# D1_-_LCD_TH_Screws.net
KiCad netlist of a schematic drawn in EAGLE
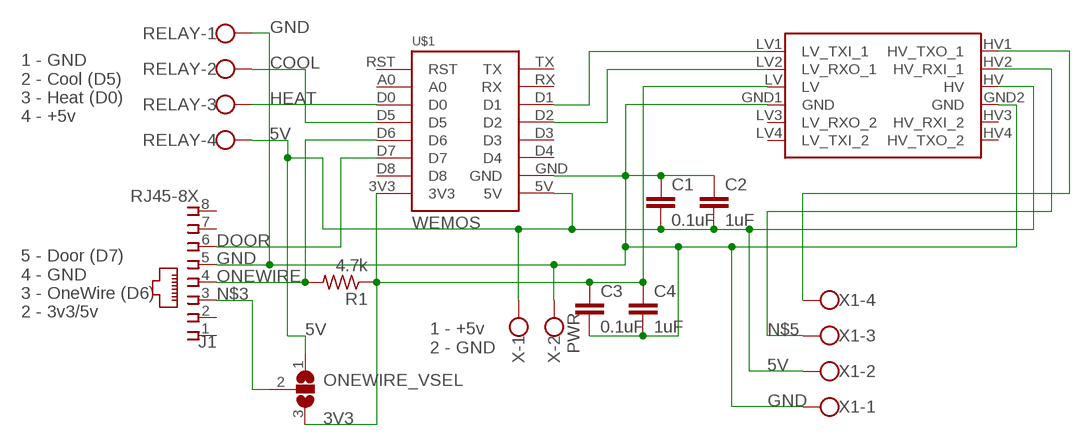
[diagram p0: schematic, sheet 1]

(export (version "E")
  (design (tool "Eeschema 10.0.6"))
  (components
    (comp (ref "C1")
      (value "0.1uF")
      (footprint "eagle-import:C050-035X075")
      (libsource (lib "eagle-import") (part "C-EU050-035X075"))
    )
    (comp (ref "C2")
      (value "1uF")
      (footprint "eagle-import:C050-035X075")
      (libsource (lib "eagle-import") (part "C-EU050-035X075"))
    )
    (comp (ref "C3")
      (value "0.1uF")
      (footprint "eagle-import:C050-035X075")
      (libsource (lib "eagle-import") (part "C-EU050-035X075"))
    )
    (comp (ref "C4")
      (value "1uF")
      (footprint "eagle-import:C050-035X075")
      (libsource (lib "eagle-import") (part "C-EU050-035X075"))
    )
    (comp (ref "J1")
      (value "RJ45-8X")
      (footprint "eagle-import:RJ45-NS-XDIM")
      (libsource (lib "eagle-import") (part "RJ45-8X"))
    )
    (comp (ref "ONEWIRE_VSEL")
      (value "SJ2WW")
      (footprint "eagle-import:SJ_2W")
      (libsource (lib "eagle-import") (part "SJ2WW"))
    )
    (comp (ref "R1")
      (value "4.7k")
      (footprint "eagle-import:0309_12")
      (libsource (lib "eagle-import") (part "R-US_0309/12"))
    )
    (comp (ref "RELAY")
      (value "W237-4")
      (footprint "eagle-import:W237-4")
      (libsource (lib "eagle-import") (part "W237-4"))
    )
    (comp (ref "U$1")
      (value "WEMOS")
      (footprint "eagle-import:WEMOS")
      (libsource (lib "eagle-import") (part "WEMOS"))
    )
    (comp (ref "U$3")
      (value "SPARKFUN_LOGIC_LEVEL_CONVERTER")
      (footprint "eagle-import:SPARKFUN_LOGIC_LEVEL_CONVERTER")
      (libsource (lib "eagle-import") (part "SPARKFUN_LOGIC_LEVEL_CONVERTER"))
    )
    (comp (ref "X")
      (value "PWR")
      (footprint "eagle-import:W237-102")
      (fields (field (name "MPN") "237-102"))
      (libsource (lib "eagle-import") (part "W237-102"))
    )
    (comp (ref "X1")
      (value "W237-4")
      (footprint "eagle-import:W237-4")
      (libsource (lib "eagle-import") (part "W237-4"))
    )
  )
  (nets
    (net (code "1") (name "/3V3") (class "Default")
      (node (ref "C3") (pin "1") (pinfunction "1_1") (pintype "passive"))
      (node (ref "C4") (pin "1") (pinfunction "1_1") (pintype "passive"))
      (node (ref "ONEWIRE_VSEL") (pin "3") (pinfunction "3_3") (pintype "passive"))
      (node (ref "R1") (pin "1") (pinfunction "1_1") (pintype "passive"))
      (node (ref "U$1") (pin "3V3") (pinfunction "3V3_3V3") (pintype "bidirectional"))
      (node (ref "U$3") (pin "LV") (pinfunction "LV_LV") (pintype "power_in"))
    )
    (net (code "2") (name "/5V") (class "Default")
      (node (ref "C1") (pin "2") (pinfunction "2_2") (pintype "passive"))
      (node (ref "C2") (pin "2") (pinfunction "2_2") (pintype "passive"))
      (node (ref "ONEWIRE_VSEL") (pin "1") (pinfunction "1_1") (pintype "passive"))
      (node (ref "RELAY") (pin "4") (pinfunction "KL_4") (pintype "passive"))
      (node (ref "U$1") (pin "5V") (pinfunction "5V_5V") (pintype "bidirectional"))
      (node (ref "U$3") (pin "HV") (pinfunction "HV_HV") (pintype "power_in"))
      (node (ref "X") (pin "1") (pinfunction "KL_1") (pintype "passive"))
      (node (ref "X1") (pin "2") (pinfunction "KL_2") (pintype "passive"))
    )
    (net (code "3") (name "/COOL") (class "Default")
      (node (ref "RELAY") (pin "2") (pinfunction "KL_2") (pintype "passive"))
      (node (ref "U$1") (pin "D5") (pinfunction "D5_D5") (pintype "bidirectional"))
    )
    (net (code "4") (name "/DOOR") (class "Default")
      (node (ref "J1") (pin "6") (pinfunction "6_6") (pintype "passive"))
      (node (ref "U$1") (pin "D7") (pinfunction "D7_D7") (pintype "bidirectional"))
    )
    (net (code "5") (name "/GND") (class "Default")
      (node (ref "C1") (pin "1") (pinfunction "1_1") (pintype "passive"))
      (node (ref "C2") (pin "1") (pinfunction "1_1") (pintype "passive"))
      (node (ref "C3") (pin "2") (pinfunction "2_2") (pintype "passive"))
      (node (ref "C4") (pin "2") (pinfunction "2_2") (pintype "passive"))
      (node (ref "J1") (pin "5") (pinfunction "5_5") (pintype "passive"))
      (node (ref "RELAY") (pin "1") (pinfunction "KL_1") (pintype "passive"))
      (node (ref "U$1") (pin "GND") (pinfunction "GND_GND") (pintype "bidirectional"))
      (node (ref "U$3") (pin "GND1") (pinfunction "GND_GND1") (pintype "power_in"))
      (node (ref "U$3") (pin "GND2") (pinfunction "GND_GND2") (pintype "power_in"))
      (node (ref "X") (pin "2") (pinfunction "KL_2") (pintype "passive"))
      (node (ref "X1") (pin "1") (pinfunction "KL_1") (pintype "passive"))
    )
    (net (code "6") (name "/HEAT") (class "Default")
      (node (ref "RELAY") (pin "3") (pinfunction "KL_3") (pintype "passive"))
      (node (ref "U$1") (pin "D0") (pinfunction "D0_D0") (pintype "bidirectional"))
    )
    (net (code "7") (name "/N$3") (class "Default")
      (node (ref "J1") (pin "3") (pinfunction "3_3") (pintype "passive"))
      (node (ref "ONEWIRE_VSEL") (pin "2") (pinfunction "2_2") (pintype "passive"))
    )
    (net (code "8") (name "/N$5") (class "Default")
      (node (ref "U$3") (pin "HV2") (pinfunction "HV_RXI_1_HV2") (pintype "bidirectional"))
      (node (ref "X1") (pin "3") (pinfunction "KL_3") (pintype "passive"))
    )
    (net (code "9") (name "/ONEWIRE") (class "Default")
      (node (ref "J1") (pin "4") (pinfunction "4_4") (pintype "passive"))
      (node (ref "R1") (pin "2") (pinfunction "2_2") (pintype "passive"))
      (node (ref "U$1") (pin "D6") (pinfunction "D6_D6") (pintype "bidirectional"))
    )
    (net (code "10") (name "Net-(U$3-HV_TXO_1)") (class "Default")
      (node (ref "U$3") (pin "HV1") (pinfunction "HV_TXO_1_HV1") (pintype "bidirectional"))
      (node (ref "X1") (pin "4") (pinfunction "KL_4") (pintype "passive"))
    )
    (net (code "11") (name "Net-(U$3-LV_RXO_1)") (class "Default")
      (node (ref "U$1") (pin "D2") (pinfunction "D2_D2") (pintype "bidirectional"))
      (node (ref "U$3") (pin "LV2") (pinfunction "LV_RXO_1_LV2") (pintype "bidirectional"))
    )
    (net (code "12") (name "Net-(U$3-LV_TXI_1)") (class "Default")
      (node (ref "U$1") (pin "D1") (pinfunction "D1_D1") (pintype "bidirectional"))
      (node (ref "U$3") (pin "LV1") (pinfunction "LV_TXI_1_LV1") (pintype "bidirectional"))
    )
    (net (code "13") (name "unconnected-(J1-Pad1)") (class "Default")
      (node (ref "J1") (pin "1") (pinfunction "1_1") (pintype "passive"))
    )
    (net (code "14") (name "unconnected-(J1-Pad2)") (class "Default")
      (node (ref "J1") (pin "2") (pinfunction "2_2") (pintype "passive"))
    )
    (net (code "15") (name "unconnected-(J1-Pad7)") (class "Default")
      (node (ref "J1") (pin "7") (pinfunction "7_7") (pintype "passive"))
    )
    (net (code "16") (name "unconnected-(J1-Pad8)") (class "Default")
      (node (ref "J1") (pin "8") (pinfunction "8_8") (pintype "passive"))
    )
    (net (code "17") (name "unconnected-(U$1-PadA0)") (class "Default")
      (node (ref "U$1") (pin "A0") (pinfunction "A0_A0") (pintype "bidirectional"))
    )
    (net (code "18") (name "unconnected-(U$1-PadD3)") (class "Default")
      (node (ref "U$1") (pin "D3") (pinfunction "D3_D3") (pintype "bidirectional"))
    )
    (net (code "19") (name "unconnected-(U$1-PadD4)") (class "Default")
      (node (ref "U$1") (pin "D4") (pinfunction "D4_D4") (pintype "bidirectional"))
    )
    (net (code "20") (name "unconnected-(U$1-PadD8)") (class "Default")
      (node (ref "U$1") (pin "D8") (pinfunction "D8_D8") (pintype "bidirectional"))
    )
    (net (code "21") (name "unconnected-(U$1-PadRST)") (class "Default")
      (node (ref "U$1") (pin "RST") (pinfunction "RST_RST") (pintype "bidirectional"))
    )
    (net (code "22") (name "unconnected-(U$1-PadRX)") (class "Default")
      (node (ref "U$1") (pin "RX") (pinfunction "RX_RX") (pintype "bidirectional"))
    )
    (net (code "23") (name "unconnected-(U$1-PadTX)") (class "Default")
      (node (ref "U$1") (pin "TX") (pinfunction "TX_TX") (pintype "bidirectional"))
    )
    (net (code "24") (name "unconnected-(U$3-HV_RXI_2-PadHV3)") (class "Default")
      (node (ref "U$3") (pin "HV3") (pinfunction "HV_RXI_2_HV3") (pintype "bidirectional"))
    )
    (net (code "25") (name "unconnected-(U$3-HV_TXO_2-PadHV4)") (class "Default")
      (node (ref "U$3") (pin "HV4") (pinfunction "HV_TXO_2_HV4") (pintype "bidirectional"))
    )
    (net (code "26") (name "unconnected-(U$3-LV_RXO_2-PadLV3)") (class "Default")
      (node (ref "U$3") (pin "LV3") (pinfunction "LV_RXO_2_LV3") (pintype "bidirectional"))
    )
    (net (code "27") (name "unconnected-(U$3-LV_TXI_2-PadLV4)") (class "Default")
      (node (ref "U$3") (pin "LV4") (pinfunction "LV_TXI_2_LV4") (pintype "bidirectional"))
    )
  )
)
